# ShieldDino.net
KiCad netlist of a schematic drawn in EAGLE
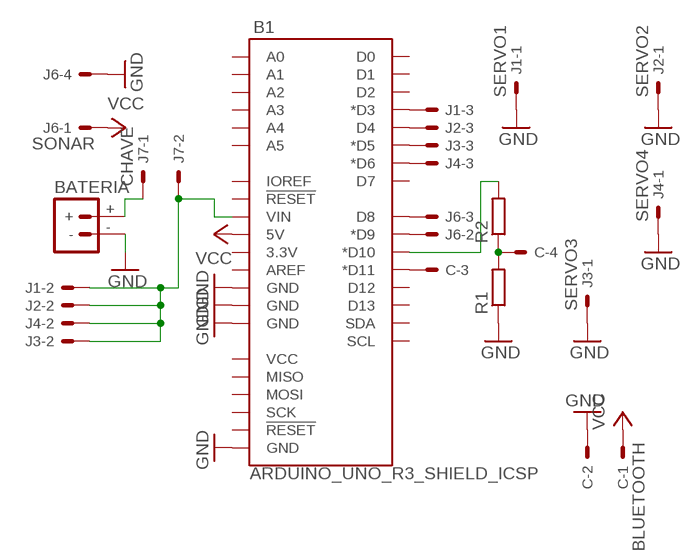
[diagram p0: schematic, sheet 1]

(export (version "E")
  (design (tool "Eeschema 10.0.6"))
  (components
    (comp (ref "B1")
      (value "ARDUINO_UNO_R3_SHIELD_ICSP")
      (footprint "eagle-import:UNO_R3_SHIELD_ICSP")
      (libsource (lib "eagle-import") (part "ARDUINO_UNO_R3_SHIELD_ICSP"))
    )
    (comp (ref "BATERIA")
      (value "BATTERY_CONNXT60")
      (footprint "eagle-import:XT60")
      (libsource (lib "eagle-import") (part "BATTERY_CONNXT60"))
    )
    (comp (ref "C")
      (value "BLUETOOTH")
      (footprint "eagle-import:6410-04")
      (libsource (lib "eagle-import") (part "CONN_0427-2041"))
    )
    (comp (ref "J1")
      (value "SERVO1")
      (footprint "eagle-import:6410-03")
      (libsource (lib "eagle-import") (part "CONN_0327-2031"))
    )
    (comp (ref "J2")
      (value "SERVO2")
      (footprint "eagle-import:6410-03")
      (libsource (lib "eagle-import") (part "CONN_0327-2031"))
    )
    (comp (ref "J3")
      (value "SERVO3")
      (footprint "eagle-import:6410-03")
      (libsource (lib "eagle-import") (part "CONN_0327-2031"))
    )
    (comp (ref "J4")
      (value "SERVO4")
      (footprint "eagle-import:6410-03")
      (libsource (lib "eagle-import") (part "CONN_0327-2031"))
    )
    (comp (ref "J6")
      (value "SONAR")
      (footprint "eagle-import:6410-04")
      (libsource (lib "eagle-import") (part "CONN_0427-2041"))
    )
    (comp (ref "J7")
      (value "CHAVE")
      (footprint "eagle-import:6410-02")
      (libsource (lib "eagle-import") (part "CONN_0227-2021"))
    )
    (comp (ref "R1")
      (value "R-EU_0204/7")
      (footprint "eagle-import:0204_7")
      (libsource (lib "eagle-import") (part "R-EU_0204/7"))
    )
    (comp (ref "R2")
      (value "R-EU_0204/7")
      (footprint "eagle-import:0204_7")
      (libsource (lib "eagle-import") (part "R-EU_0204/7"))
    )
  )
  (nets
    (net (code "1") (name "GND") (class "Default")
      (node (ref "B1") (pin "GND@0") (pinfunction "GND_GND@0") (pintype "bidirectional"))
      (node (ref "B1") (pin "GND@1") (pinfunction "GND_GND@1") (pintype "bidirectional"))
      (node (ref "B1") (pin "GND@2") (pinfunction "GND_GND@2") (pintype "bidirectional"))
      (node (ref "B1") (pin "GND_ICSP") (pinfunction "GND_GND_ICSP") (pintype "bidirectional"))
      (node (ref "BATERIA") (pin "-") (pinfunction "-_-") (pintype "passive"))
      (node (ref "C") (pin "2") (pinfunction "S_2") (pintype "passive"))
      (node (ref "J1") (pin "1") (pinfunction "S_1") (pintype "passive"))
      (node (ref "J2") (pin "1") (pinfunction "S_1") (pintype "passive"))
      (node (ref "J3") (pin "1") (pinfunction "S_1") (pintype "passive"))
      (node (ref "J4") (pin "1") (pinfunction "S_1") (pintype "passive"))
      (node (ref "J6") (pin "4") (pinfunction "S_4") (pintype "passive"))
      (node (ref "R1") (pin "1") (pinfunction "1_1") (pintype "passive"))
    )
    (net (code "2") (name "Net-(B1-*D3)") (class "Default")
      (node (ref "B1") (pin "D3") (pinfunction "*D3_D3") (pintype "bidirectional"))
      (node (ref "J1") (pin "3") (pinfunction "S_3") (pintype "passive"))
    )
    (net (code "3") (name "Net-(B1-*D5)") (class "Default")
      (node (ref "B1") (pin "D5") (pinfunction "*D5_D5") (pintype "bidirectional"))
      (node (ref "J3") (pin "3") (pinfunction "S_3") (pintype "passive"))
    )
    (net (code "4") (name "Net-(B1-*D6)") (class "Default")
      (node (ref "B1") (pin "D6") (pinfunction "*D6_D6") (pintype "bidirectional"))
      (node (ref "J4") (pin "3") (pinfunction "S_3") (pintype "passive"))
    )
    (net (code "5") (name "Net-(B1-*D9)") (class "Default")
      (node (ref "B1") (pin "D9") (pinfunction "*D9_D9") (pintype "bidirectional"))
      (node (ref "J6") (pin "2") (pinfunction "S_2") (pintype "passive"))
    )
    (net (code "6") (name "Net-(B1-*D10)") (class "Default")
      (node (ref "B1") (pin "D10") (pinfunction "*D10_D10") (pintype "bidirectional"))
      (node (ref "R2") (pin "2") (pinfunction "2_2") (pintype "passive"))
    )
    (net (code "7") (name "Net-(B1-*D11)") (class "Default")
      (node (ref "B1") (pin "D11") (pinfunction "*D11_D11") (pintype "bidirectional"))
      (node (ref "C") (pin "3") (pinfunction "S_3") (pintype "passive"))
    )
    (net (code "8") (name "Net-(CD-S)") (class "Default")
      (node (ref "C") (pin "4") (pinfunction "S_4") (pintype "passive"))
      (node (ref "R1") (pin "2") (pinfunction "2_2") (pintype "passive"))
      (node (ref "R2") (pin "1") (pinfunction "1_1") (pintype "passive"))
    )
    (net (code "9") (name "Net-(J1B-S)") (class "Default")
      (node (ref "B1") (pin "VIN") (pinfunction "VIN_VIN") (pintype "bidirectional"))
      (node (ref "J1") (pin "2") (pinfunction "S_2") (pintype "passive"))
      (node (ref "J2") (pin "2") (pinfunction "S_2") (pintype "passive"))
      (node (ref "J3") (pin "2") (pinfunction "S_2") (pintype "passive"))
      (node (ref "J4") (pin "2") (pinfunction "S_2") (pintype "passive"))
      (node (ref "J7") (pin "2") (pinfunction "S_2") (pintype "passive"))
    )
    (net (code "10") (name "Net-(J2C-S)") (class "Default")
      (node (ref "B1") (pin "D4") (pinfunction "D4_D4") (pintype "bidirectional"))
      (node (ref "J2") (pin "3") (pinfunction "S_3") (pintype "passive"))
    )
    (net (code "11") (name "Net-(J6C-S)") (class "Default")
      (node (ref "B1") (pin "D8") (pinfunction "D8_D8") (pintype "bidirectional"))
      (node (ref "J6") (pin "3") (pinfunction "S_3") (pintype "passive"))
    )
    (net (code "12") (name "Net-(J7A-S)") (class "Default")
      (node (ref "BATERIA") (pin "+") (pinfunction "+_+") (pintype "passive"))
      (node (ref "J7") (pin "1") (pinfunction "S_1") (pintype "passive"))
    )
    (net (code "13") (name "VCC") (class "Default")
      (node (ref "B1") (pin "5V") (pinfunction "5V_5V") (pintype "bidirectional"))
      (node (ref "C") (pin "1") (pinfunction "S_1") (pintype "passive"))
      (node (ref "J6") (pin "1") (pinfunction "S_1") (pintype "passive"))
    )
    (net (code "14") (name "unconnected-(B1-D0-PadRX)") (class "Default")
      (node (ref "B1") (pin "RX") (pinfunction "D0_RX") (pintype "bidirectional"))
    )
    (net (code "15") (name "unconnected-(B1-D1-PadTX)") (class "Default")
      (node (ref "B1") (pin "TX") (pinfunction "D1_TX") (pintype "bidirectional"))
    )
    (net (code "16") (name "unconnected-(B1-Pad3.3V)") (class "Default")
      (node (ref "B1") (pin "3.3V") (pinfunction "3.3V_3.3V") (pintype "bidirectional"))
    )
    (net (code "17") (name "unconnected-(B1-PadA0)") (class "Default")
      (node (ref "B1") (pin "A0") (pinfunction "A0_A0") (pintype "bidirectional"))
    )
    (net (code "18") (name "unconnected-(B1-PadA1)") (class "Default")
      (node (ref "B1") (pin "A1") (pinfunction "A1_A1") (pintype "bidirectional"))
    )
    (net (code "19") (name "unconnected-(B1-PadA2)") (class "Default")
      (node (ref "B1") (pin "A2") (pinfunction "A2_A2") (pintype "bidirectional"))
    )
    (net (code "20") (name "unconnected-(B1-PadA3)") (class "Default")
      (node (ref "B1") (pin "A3") (pinfunction "A3_A3") (pintype "bidirectional"))
    )
    (net (code "21") (name "unconnected-(B1-PadA4)") (class "Default")
      (node (ref "B1") (pin "A4") (pinfunction "A4_A4") (pintype "bidirectional"))
    )
    (net (code "22") (name "unconnected-(B1-PadA5)") (class "Default")
      (node (ref "B1") (pin "A5") (pinfunction "A5_A5") (pintype "bidirectional"))
    )
    (net (code "23") (name "unconnected-(B1-PadAREF)") (class "Default")
      (node (ref "B1") (pin "AREF") (pinfunction "AREF_AREF") (pintype "bidirectional"))
    )
    (net (code "24") (name "unconnected-(B1-PadD2)") (class "Default")
      (node (ref "B1") (pin "D2") (pinfunction "D2_D2") (pintype "bidirectional"))
    )
    (net (code "25") (name "unconnected-(B1-PadD7)") (class "Default")
      (node (ref "B1") (pin "D7") (pinfunction "D7_D7") (pintype "bidirectional"))
    )
    (net (code "26") (name "unconnected-(B1-PadD12)") (class "Default")
      (node (ref "B1") (pin "D12") (pinfunction "D12_D12") (pintype "bidirectional"))
    )
    (net (code "27") (name "unconnected-(B1-PadD13)") (class "Default")
      (node (ref "B1") (pin "D13") (pinfunction "D13_D13") (pintype "bidirectional"))
    )
    (net (code "28") (name "unconnected-(B1-PadIOREF)") (class "Default")
      (node (ref "B1") (pin "IOREF") (pinfunction "IOREF_IOREF") (pintype "bidirectional"))
    )
    (net (code "29") (name "unconnected-(B1-PadMISO)") (class "Default")
      (node (ref "B1") (pin "MISO") (pinfunction "MISO_MISO") (pintype "bidirectional"))
    )
    (net (code "30") (name "unconnected-(B1-PadMOSI)") (class "Default")
      (node (ref "B1") (pin "MOSI") (pinfunction "MOSI_MOSI") (pintype "bidirectional"))
    )
    (net (code "31") (name "unconnected-(B1-PadSCK)") (class "Default")
      (node (ref "B1") (pin "SCK") (pinfunction "SCK_SCK") (pintype "bidirectional"))
    )
    (net (code "32") (name "unconnected-(B1-PadSCL)") (class "Default")
      (node (ref "B1") (pin "SCL") (pinfunction "SCL_SCL") (pintype "bidirectional"))
    )
    (net (code "33") (name "unconnected-(B1-PadSDA)") (class "Default")
      (node (ref "B1") (pin "SDA") (pinfunction "SDA_SDA") (pintype "bidirectional"))
    )
    (net (code "34") (name "unconnected-(B1-VCC-Pad5V_ICSP)") (class "Default")
      (node (ref "B1") (pin "5V_ICSP") (pinfunction "VCC_5V_ICSP") (pintype "bidirectional"))
    )
    (net (code "35") (name "unconnected-(B1-~{RESET}-PadRES)") (class "Default")
      (node (ref "B1") (pin "RES") (pinfunction "~{RESET}_RES") (pintype "bidirectional"))
    )
    (net (code "36") (name "unconnected-(B1-~{RESET}-PadRST_ICSP)") (class "Default")
      (node (ref "B1") (pin "RST_ICSP") (pinfunction "~{RESET}_RST_ICSP") (pintype "bidirectional"))
    )
  )
)
